# Y9A_4_5050.net
KiCad netlist of a schematic drawn in Altium Designer
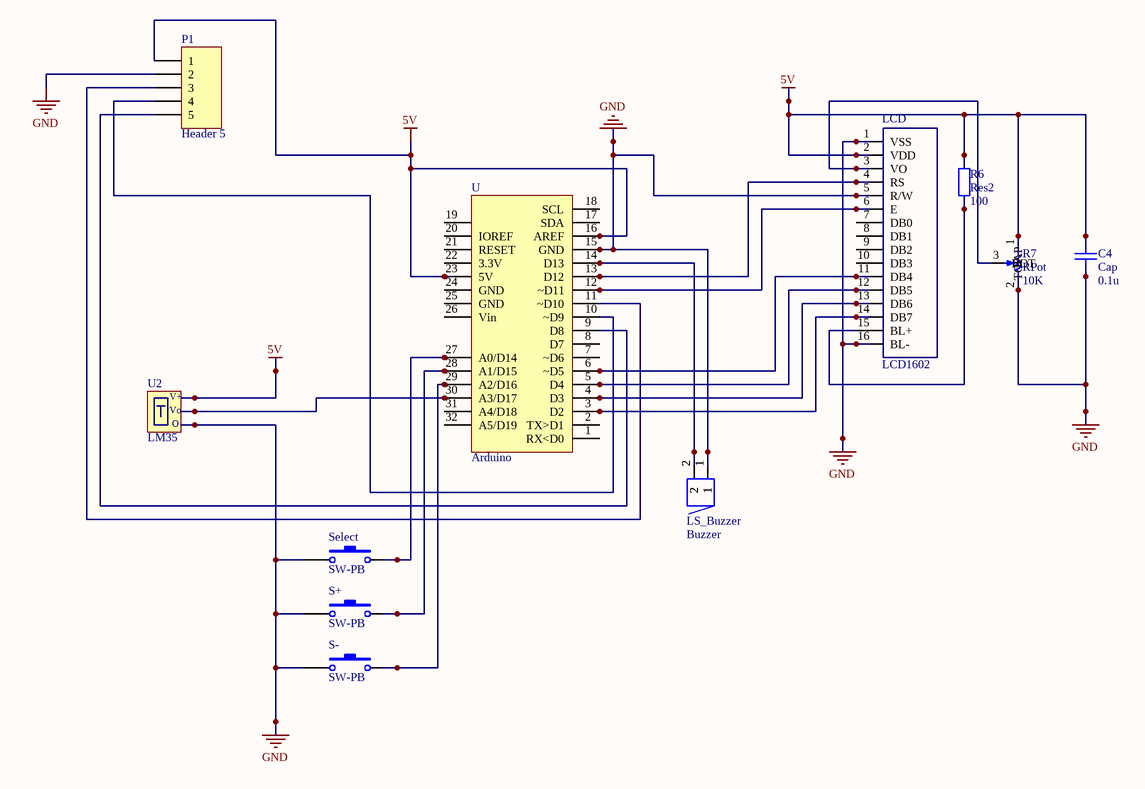
[diagram p0: Y9A_4_5050.SchDoc]

(export (version "E")
  (design (tool "Eeschema 10.0.6"))
  (components
    (comp (ref "C4")
      (value "Cap")
      (footprint "RAD-0.3")
      (description "Capacitor")
      (fields (field (name "ALTIUM_VALUE") "0.1u") (field (name "PUBLISHER") "Altium Limited"))
      (libsource (lib "Miscellaneous Devices") (part "Cap"))
    )
    (comp (ref "LCD") (value "LCD1602") (footprint "LCD1602") (libsource (lib "LCD") (part "LCD1602")))
    (comp (ref "LS_Buzzer")
      (value "Buzzer")
      (footprint "Buzzer")
      (description "Magnetic Transducer Buzzer")
      (fields (field (name "PUBLISHER") "Altium Limited"))
      (libsource (lib "Miscellaneous Devices") (part "Buzzer"))
    )
    (comp (ref "P1")
      (value "Header 5")
      (footprint "HDR1X5")
      (description "Header, 5-Pin")
      (fields (field (name "PUBLISHER") "Altium Limited"))
      (libsource (lib "Miscellaneous Connectors") (part "Header 5"))
    )
    (comp (ref "R6")
      (value "Res2")
      (footprint "AXIAL-0.4")
      (description "Resistor")
      (fields (field (name "ALTIUM_VALUE") "100") (field (name "PUBLISHER") "Altium Limited"))
      (libsource (lib "Miscellaneous Devices") (part "Res2"))
    )
    (comp (ref "R7")
      (value "RPot")
      (footprint "RP-W")
      (description "Potentiometer")
      (fields (field (name "ALTIUM_VALUE") "10K") (field (name "PUBLISHER") "Altium Limited"))
      (libsource (lib "Miscellaneous Devices") (part "RPot"))
    )
    (comp (ref "S+")
      (value "SW-PB")
      (footprint "AN-S")
      (description "Switch")
      (fields (field (name "PUBLISHER") "Altium Limited"))
      (libsource (lib "Miscellaneous Devices") (part "SW-PB"))
    )
    (comp (ref "S-")
      (value "SW-PB")
      (footprint "AN-S")
      (description "Switch")
      (fields (field (name "PUBLISHER") "Altium Limited"))
      (libsource (lib "Miscellaneous Devices") (part "SW-PB"))
    )
    (comp (ref "Select")
      (value "SW-PB")
      (footprint "AN-S")
      (description "Switch")
      (fields (field (name "PUBLISHER") "Altium Limited"))
      (libsource (lib "Miscellaneous Devices") (part "SW-PB"))
    )
    (comp (ref "U")
      (value "Arduino")
      (footprint "Arduino-UNO-EX")
      (libsource (lib "LixhSch-N") (part "Arduino-UNO-EX"))
    )
    (comp (ref "U2")
      (value "LM35")
      (footprint "LM35")
      (description "LM35温度传感器")
      (libsource (lib "LixhSch") (part "LM35"))
    )
  )
  (nets
    (net (code "1") (name "5V") (class "Default")
      (node (ref "C4") (pin "2") (pinfunction "2_2") (pintype "passive"))
      (node (ref "LCD") (pin "2") (pinfunction "VDD_2") (pintype "passive"))
      (node (ref "P1") (pin "1") (pinfunction "1_1") (pintype "passive"))
      (node (ref "R6") (pin "2") (pinfunction "2_2") (pintype "passive"))
      (node (ref "R7") (pin "1") (pinfunction "TOP_1") (pintype "passive"))
      (node (ref "U") (pin "16") (pinfunction "AREF_16") (pintype "power_in"))
      (node (ref "U") (pin "23") (pinfunction "5V_23") (pintype "power_in"))
      (node (ref "U2") (pin "1") (pinfunction "1_1") (pintype "power_in"))
    )
    (net (code "2") (name "GND") (class "Default")
      (node (ref "C4") (pin "1") (pinfunction "1_1") (pintype "passive"))
      (node (ref "LCD") (pin "1") (pinfunction "VSS_1") (pintype "passive"))
      (node (ref "LCD") (pin "16") (pinfunction "BL-_16") (pintype "passive"))
      (node (ref "LCD") (pin "5") (pinfunction "R/W_5") (pintype "passive"))
      (node (ref "LS_Buzzer") (pin "1") (pinfunction "1_1") (pintype "passive"))
      (node (ref "P1") (pin "2") (pinfunction "2_2") (pintype "passive"))
      (node (ref "R7") (pin "2") (pinfunction "TAP_2") (pintype "passive"))
      (node (ref "S+") (pin "1") (pinfunction "1_1") (pintype "passive"))
      (node (ref "S-") (pin "1") (pinfunction "1_1") (pintype "passive"))
      (node (ref "Select") (pin "1") (pinfunction "1_1") (pintype "passive"))
      (node (ref "U") (pin "15") (pinfunction "GND_15") (pintype "power_in"))
      (node (ref "U2") (pin "3") (pinfunction "3_3") (pintype "power_in"))
    )
    (net (code "3") (name "Net-(LCD-BL+)") (class "Default")
      (node (ref "LCD") (pin "15") (pinfunction "BL+_15") (pintype "passive"))
      (node (ref "R6") (pin "1") (pinfunction "1_1") (pintype "passive"))
    )
    (net (code "4") (name "Net-(LCD-DB4)") (class "Default")
      (node (ref "LCD") (pin "11") (pinfunction "DB4_11") (pintype "passive"))
      (node (ref "U") (pin "6") (pinfunction "~D5_6") (pintype "power_in"))
    )
    (net (code "5") (name "Net-(LCD-DB5)") (class "Default")
      (node (ref "LCD") (pin "12") (pinfunction "DB5_12") (pintype "passive"))
      (node (ref "U") (pin "5") (pinfunction "D4_5") (pintype "power_in"))
    )
    (net (code "6") (name "Net-(LCD-DB6)") (class "Default")
      (node (ref "LCD") (pin "13") (pinfunction "DB6_13") (pintype "passive"))
      (node (ref "U") (pin "4") (pinfunction "D3_4") (pintype "power_in"))
    )
    (net (code "7") (name "Net-(LCD-DB7)") (class "Default")
      (node (ref "LCD") (pin "14") (pinfunction "DB7_14") (pintype "passive"))
      (node (ref "U") (pin "3") (pinfunction "D2_3") (pintype "power_in"))
    )
    (net (code "8") (name "Net-(LCD-E)") (class "Default")
      (node (ref "LCD") (pin "6") (pinfunction "E_6") (pintype "passive"))
      (node (ref "U") (pin "12") (pinfunction "~D11_12") (pintype "power_in"))
    )
    (net (code "9") (name "Net-(LCD-RS)") (class "Default")
      (node (ref "LCD") (pin "4") (pinfunction "RS_4") (pintype "passive"))
      (node (ref "U") (pin "13") (pinfunction "D12_13") (pintype "power_in"))
    )
    (net (code "10") (name "Net-(LCD-VO)") (class "Default")
      (node (ref "LCD") (pin "3") (pinfunction "VO_3") (pintype "passive"))
      (node (ref "R7") (pin "3") (pinfunction "BOT_3") (pintype "passive"))
    )
    (net (code "11") (name "Net-(U-A0{slash}D14)") (class "Default")
      (node (ref "Select") (pin "2") (pinfunction "2_2") (pintype "passive"))
      (node (ref "U") (pin "27") (pinfunction "A0/D14_27") (pintype "power_in"))
    )
    (net (code "12") (name "Net-(U-A1{slash}D15)") (class "Default")
      (node (ref "S+") (pin "2") (pinfunction "2_2") (pintype "passive"))
      (node (ref "U") (pin "28") (pinfunction "A1/D15_28") (pintype "power_in"))
    )
    (net (code "13") (name "Net-(U-A2{slash}D16)") (class "Default")
      (node (ref "S-") (pin "2") (pinfunction "2_2") (pintype "passive"))
      (node (ref "U") (pin "29") (pinfunction "A2/D16_29") (pintype "power_in"))
    )
    (net (code "14") (name "Net-(U-A3{slash}D17)") (class "Default")
      (node (ref "U") (pin "30") (pinfunction "A3/D17_30") (pintype "power_in"))
      (node (ref "U2") (pin "2") (pinfunction "2_2") (pintype "passive"))
    )
    (net (code "15") (name "Net-(U-D8)") (class "Default")
      (node (ref "P1") (pin "5") (pinfunction "5_5") (pintype "passive"))
      (node (ref "U") (pin "9") (pinfunction "D8_9") (pintype "power_in"))
    )
    (net (code "16") (name "Net-(U-D13)") (class "Default")
      (node (ref "LS_Buzzer") (pin "2") (pinfunction "2_2") (pintype "passive"))
      (node (ref "U") (pin "14") (pinfunction "D13_14") (pintype "power_in"))
    )
    (net (code "17") (name "Net-(U-~D9)") (class "Default")
      (node (ref "P1") (pin "4") (pinfunction "4_4") (pintype "passive"))
      (node (ref "U") (pin "10") (pinfunction "~D9_10") (pintype "power_in"))
    )
    (net (code "18") (name "Net-(U-~D10)") (class "Default")
      (node (ref "P1") (pin "3") (pinfunction "3_3") (pintype "passive"))
      (node (ref "U") (pin "11") (pinfunction "~D10_11") (pintype "power_in"))
    )
    (net (code "19") (name "unconnected-(LCD-DB0-Pad7)") (class "Default")
      (node (ref "LCD") (pin "7") (pinfunction "DB0_7") (pintype "passive"))
    )
    (net (code "20") (name "unconnected-(LCD-DB1-Pad8)") (class "Default")
      (node (ref "LCD") (pin "8") (pinfunction "DB1_8") (pintype "passive"))
    )
    (net (code "21") (name "unconnected-(LCD-DB2-Pad9)") (class "Default")
      (node (ref "LCD") (pin "9") (pinfunction "DB2_9") (pintype "passive"))
    )
    (net (code "22") (name "unconnected-(LCD-DB3-Pad10)") (class "Default")
      (node (ref "LCD") (pin "10") (pinfunction "DB3_10") (pintype "passive"))
    )
    (net (code "23") (name "unconnected-(U-3.3V-Pad22)") (class "Default")
      (node (ref "U") (pin "22") (pinfunction "3.3V_22") (pintype "power_in"))
    )
    (net (code "24") (name "unconnected-(U-A4{slash}D18-Pad31)") (class "Default")
      (node (ref "U") (pin "31") (pinfunction "A4/D18_31") (pintype "power_in"))
    )
    (net (code "25") (name "unconnected-(U-A5{slash}D19-Pad32)") (class "Default")
      (node (ref "U") (pin "32") (pinfunction "A5/D19_32") (pintype "power_in"))
    )
    (net (code "26") (name "unconnected-(U-D7-Pad8)") (class "Default")
      (node (ref "U") (pin "8") (pinfunction "D7_8") (pintype "power_in"))
    )
    (net (code "27") (name "unconnected-(U-GND-Pad24)") (class "Default")
      (node (ref "U") (pin "24") (pinfunction "GND_24") (pintype "power_in"))
    )
    (net (code "28") (name "unconnected-(U-GND-Pad25)") (class "Default")
      (node (ref "U") (pin "25") (pinfunction "GND_25") (pintype "power_in"))
    )
    (net (code "29") (name "unconnected-(U-IOREF-Pad20)") (class "Default")
      (node (ref "U") (pin "20") (pinfunction "IOREF_20") (pintype "power_in"))
    )
    (net (code "30") (name "unconnected-(U-Pad19)") (class "Default")
      (node (ref "U") (pin "19") (pintype "power_in"))
    )
    (net (code "31") (name "unconnected-(U-RESET-Pad21)") (class "Default")
      (node (ref "U") (pin "21") (pinfunction "RESET_21") (pintype "power_in"))
    )
    (net (code "32") (name "unconnected-(U-RX<D0-Pad1)") (class "Default")
      (node (ref "U") (pin "1") (pinfunction "RX<D0_1") (pintype "power_in"))
    )
    (net (code "33") (name "unconnected-(U-SCL-Pad18)") (class "Default")
      (node (ref "U") (pin "18") (pinfunction "SCL_18") (pintype "power_in"))
    )
    (net (code "34") (name "unconnected-(U-SDA-Pad17)") (class "Default")
      (node (ref "U") (pin "17") (pinfunction "SDA_17") (pintype "power_in"))
    )
    (net (code "35") (name "unconnected-(U-TX>D1-Pad2)") (class "Default")
      (node (ref "U") (pin "2") (pinfunction "TX>D1_2") (pintype "power_in"))
    )
    (net (code "36") (name "unconnected-(U-Vin-Pad26)") (class "Default")
      (node (ref "U") (pin "26") (pinfunction "Vin_26") (pintype "power_in"))
    )
    (net (code "37") (name "unconnected-(U-~D6-Pad7)") (class "Default")
      (node (ref "U") (pin "7") (pinfunction "~D6_7") (pintype "power_in"))
    )
  )
)
